# LCDTFT_CTRL_FT801.net
KiCad netlist of a schematic drawn in Altium Designer
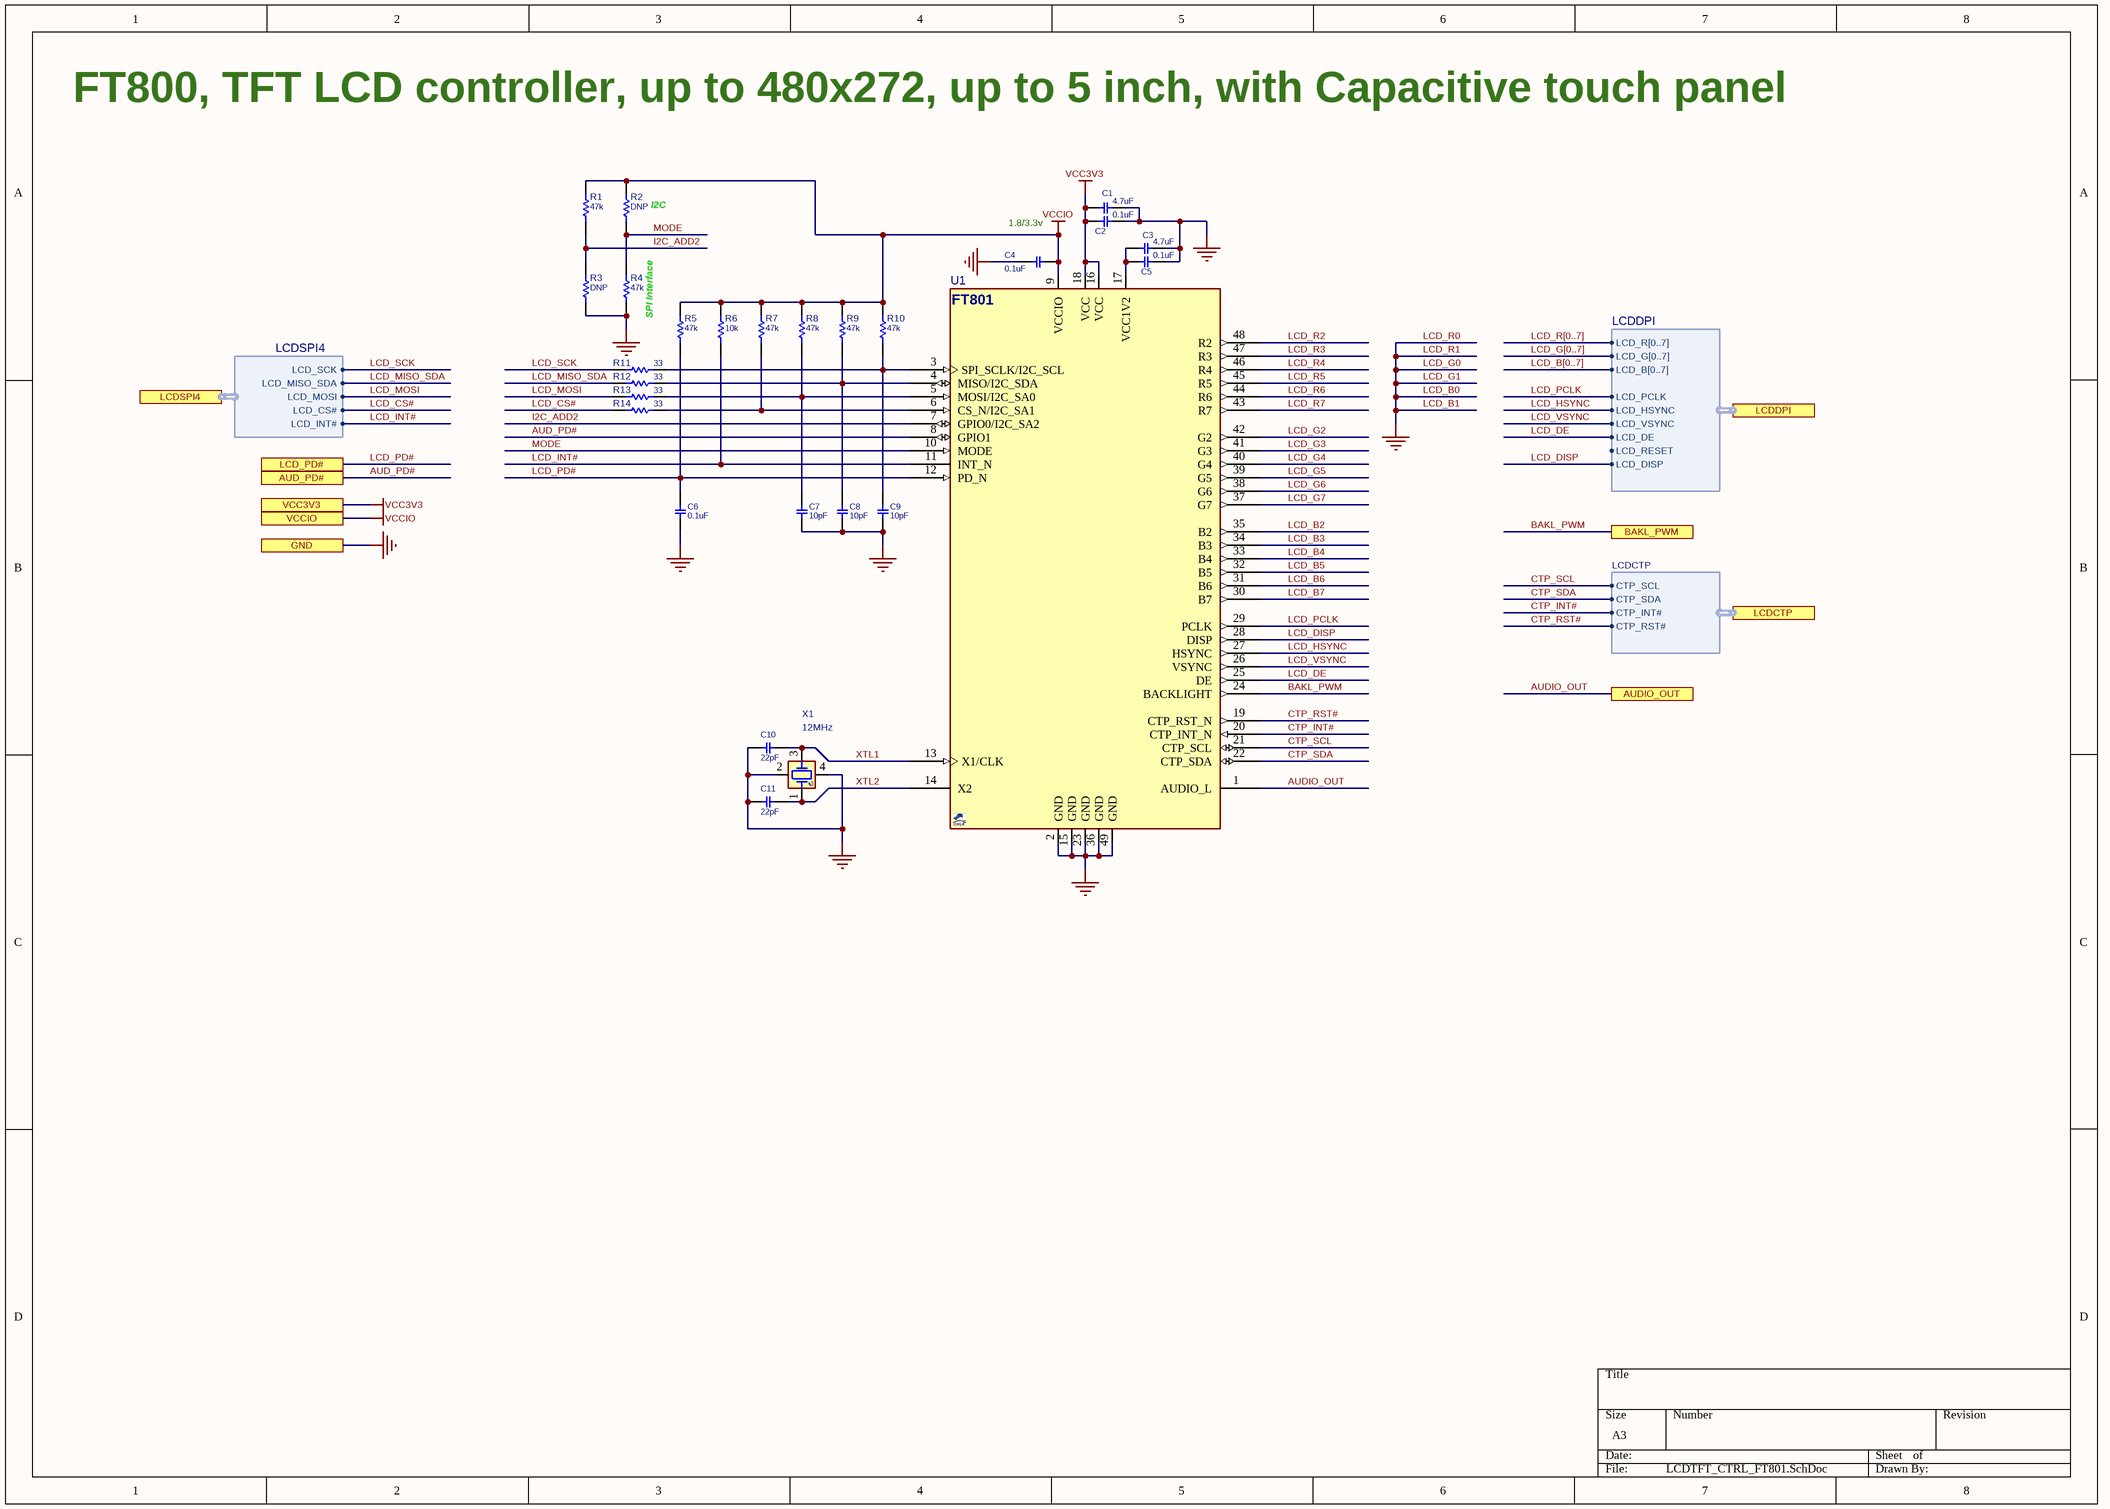
[diagram p0: LCDTFT_CTRL_FT801.SchDoc]

(export (version "E")
  (design (tool "Eeschema 10.0.6"))
  (components
    (comp (ref "C1")
      (value "4.7uF")
      (footprint "C0603")
      (description "CAP, MLCC")
      (libsource (lib "passive_smd") (part "CAP_SMD_MLCC"))
    )
    (comp (ref "C2")
      (value "0.1uF")
      (footprint "C0402")
      (description "CAP, MLCC")
      (fields (field (name "MANF_P#") "GRM155R71H104KE14D") (field (name "MANF") "Murata"))
      (libsource (lib "passive_smd") (part "CAP_SMD_MLCC"))
    )
    (comp (ref "C3")
      (value "4.7uF")
      (footprint "C0603")
      (description "CAP, MLCC")
      (libsource (lib "passive_smd") (part "CAP_SMD_MLCC"))
    )
    (comp (ref "C4")
      (value "0.1uF")
      (footprint "C0402")
      (description "CAP, MLCC")
      (fields (field (name "MANF_P#") "GRM155R71H104KE14D") (field (name "MANF") "Murata"))
      (libsource (lib "passive_smd") (part "CAP_SMD_MLCC"))
    )
    (comp (ref "C5")
      (value "0.1uF")
      (footprint "C0402")
      (description "CAP, MLCC")
      (fields (field (name "MANF_P#") "GRM155R71H104KE14D") (field (name "MANF") "Murata"))
      (libsource (lib "passive_smd") (part "CAP_SMD_MLCC"))
    )
    (comp (ref "C6")
      (value "0.1uF")
      (footprint "C0402")
      (description "CAP, MLCC")
      (fields (field (name "MANF_P#") "GRM155R71H104KE14D") (field (name "MANF") "Murata"))
      (libsource (lib "passive_smd") (part "CAP_SMD_MLCC"))
    )
    (comp (ref "C7")
      (value "10pF")
      (footprint "C0402")
      (description "CAP, MLCC")
      (libsource (lib "passive_smd") (part "CAP_SMD_MLCC"))
    )
    (comp (ref "C8")
      (value "10pF")
      (footprint "C0402")
      (description "CAP, MLCC")
      (libsource (lib "passive_smd") (part "CAP_SMD_MLCC"))
    )
    (comp (ref "C9")
      (value "10pF")
      (footprint "C0402")
      (description "CAP, MLCC")
      (libsource (lib "passive_smd") (part "CAP_SMD_MLCC"))
    )
    (comp (ref "C10")
      (value "22pF")
      (footprint "C0402")
      (description "CAP, MLCC")
      (libsource (lib "passive_smd") (part "CAP_SMD_MLCC"))
    )
    (comp (ref "C11")
      (value "22pF")
      (footprint "C0402")
      (description "CAP, MLCC")
      (libsource (lib "passive_smd") (part "CAP_SMD_MLCC"))
    )
    (comp (ref "R1")
      (value "47k")
      (footprint "R0402")
      (description "RESISTOR, SMD")
      (libsource (lib "passive_res_smd") (part "RES_SMD"))
    )
    (comp (ref "R2")
      (value "DNP")
      (footprint "R0402")
      (description "RESISTOR, SMD")
      (libsource (lib "passive_res_smd") (part "RES_SMD"))
    )
    (comp (ref "R3")
      (value "DNP")
      (footprint "R0402")
      (description "RESISTOR, SMD")
      (libsource (lib "passive_res_smd") (part "RES_SMD"))
    )
    (comp (ref "R4")
      (value "47k")
      (footprint "R0402")
      (description "RESISTOR, SMD")
      (libsource (lib "passive_res_smd") (part "RES_SMD"))
    )
    (comp (ref "R5")
      (value "47k")
      (footprint "R0402")
      (description "RESISTOR, SMD")
      (libsource (lib "passive_res_smd") (part "RES_SMD"))
    )
    (comp (ref "R6")
      (value "10k")
      (footprint "R0402")
      (description "RESISTOR, SMD")
      (libsource (lib "passive_res_smd") (part "RES_SMD"))
    )
    (comp (ref "R7")
      (value "47k")
      (footprint "R0402")
      (description "RESISTOR, SMD")
      (libsource (lib "passive_res_smd") (part "RES_SMD"))
    )
    (comp (ref "R8")
      (value "47k")
      (footprint "R0402")
      (description "RESISTOR, SMD")
      (libsource (lib "passive_res_smd") (part "RES_SMD"))
    )
    (comp (ref "R9")
      (value "47k")
      (footprint "R0402")
      (description "RESISTOR, SMD")
      (libsource (lib "passive_res_smd") (part "RES_SMD"))
    )
    (comp (ref "R10")
      (value "47k")
      (footprint "R0402")
      (description "RESISTOR, SMD")
      (libsource (lib "passive_res_smd") (part "RES_SMD"))
    )
    (comp (ref "R11")
      (value "33")
      (footprint "R0402")
      (description "RESISTOR, SMD")
      (libsource (lib "passive_res_smd") (part "RES_SMD"))
    )
    (comp (ref "R12")
      (value "33")
      (footprint "R0402")
      (description "RESISTOR, SMD")
      (libsource (lib "passive_res_smd") (part "RES_SMD"))
    )
    (comp (ref "R13")
      (value "33")
      (footprint "R0402")
      (description "RESISTOR, SMD")
      (libsource (lib "passive_res_smd") (part "RES_SMD"))
    )
    (comp (ref "R14")
      (value "33")
      (footprint "R0402")
      (description "RESISTOR, SMD")
      (libsource (lib "passive_res_smd") (part "RES_SMD"))
    )
    (comp (ref "U1")
      (value "FT801")
      (footprint "QFN50_48T")
      (description "LCD Display Controller, Embedded Video Engine, QFN-48")
      (fields (field (name "MANF") "FTDI/Bridgetek") (field (name "MANF_P#") "FT801Q"))
      (libsource (lib "lcdtft_controller") (part "FT801_QFN48"))
    )
    (comp (ref "X1")
      (value "12MHz")
      (footprint "XTL_4_3225")
      (description "Crystal 12MHz")
      (fields (field (name "MANF") "ECS") (field (name "MANF_P#") "ECS-120-18-33-JEM-TR"))
      (libsource (lib "crystal") (part "XTL_4_12MHz_3225"))
    )
  )
  (nets
    (net (code "4") (name "/AUDIO_OUT") (class "Default")
      (node (ref "U1") (pin "1") (pinfunction "AUDIO_L_1") (pintype "tri_state"))
    )
    (net (code "5") (name "/AUD_PD#") (class "Default")
      (node (ref "U1") (pin "8") (pinfunction "GPIO1_8") (pintype "bidirectional"))
    )
    (net (code "6") (name "/BAKL_PWM") (class "Default")
      (node (ref "U1") (pin "24") (pinfunction "BACKLIGHT_24") (pintype "output"))
    )
    (net (code "7") (name "/CTP_INT#") (class "Default")
      (node (ref "U1") (pin "20") (pinfunction "CTP_INT_N_20") (pintype "input"))
    )
    (net (code "8") (name "/CTP_RST#") (class "Default")
      (node (ref "U1") (pin "19") (pinfunction "CTP_RST_N_19") (pintype "output"))
    )
    (net (code "9") (name "/CTP_SCL") (class "Default")
      (node (ref "U1") (pin "21") (pinfunction "CTP_SCL_21") (pintype "bidirectional"))
    )
    (net (code "10") (name "/CTP_SDA") (class "Default")
      (node (ref "U1") (pin "22") (pinfunction "CTP_SDA_22") (pintype "bidirectional"))
    )
    (net (code "11") (name "/I2C_ADD2") (class "Default")
      (node (ref "R1") (pin "2") (pinfunction "2_2") (pintype "passive"))
      (node (ref "R3") (pin "1") (pinfunction "1_1") (pintype "passive"))
      (node (ref "U1") (pin "7") (pinfunction "GPIO0/I2C_SA2_7") (pintype "bidirectional"))
    )
    (net (code "12") (name "/LCD_B2") (class "Default")
      (node (ref "U1") (pin "35") (pinfunction "B2_35") (pintype "output"))
    )
    (net (code "13") (name "/LCD_B3") (class "Default")
      (node (ref "U1") (pin "34") (pinfunction "B3_34") (pintype "output"))
    )
    (net (code "14") (name "/LCD_B4") (class "Default")
      (node (ref "U1") (pin "33") (pinfunction "B4_33") (pintype "output"))
    )
    (net (code "15") (name "/LCD_B5") (class "Default")
      (node (ref "U1") (pin "32") (pinfunction "B5_32") (pintype "output"))
    )
    (net (code "16") (name "/LCD_B6") (class "Default")
      (node (ref "U1") (pin "31") (pinfunction "B6_31") (pintype "output"))
    )
    (net (code "17") (name "/LCD_B7") (class "Default")
      (node (ref "U1") (pin "30") (pinfunction "B7_30") (pintype "output"))
    )
    (net (code "19") (name "/LCD_CS#") (class "Default")
      (node (ref "R14") (pin "1") (pinfunction "1_1") (pintype "passive"))
    )
    (net (code "20") (name "/LCD_DE") (class "Default")
      (node (ref "U1") (pin "25") (pinfunction "DE_25") (pintype "output"))
    )
    (net (code "21") (name "/LCD_DISP") (class "Default")
      (node (ref "U1") (pin "28") (pinfunction "DISP_28") (pintype "output"))
    )
    (net (code "22") (name "/LCD_G2") (class "Default")
      (node (ref "U1") (pin "42") (pinfunction "G2_42") (pintype "output"))
    )
    (net (code "23") (name "/LCD_G3") (class "Default")
      (node (ref "U1") (pin "41") (pinfunction "G3_41") (pintype "output"))
    )
    (net (code "24") (name "/LCD_G4") (class "Default")
      (node (ref "U1") (pin "40") (pinfunction "G4_40") (pintype "output"))
    )
    (net (code "25") (name "/LCD_G5") (class "Default")
      (node (ref "U1") (pin "39") (pinfunction "G5_39") (pintype "output"))
    )
    (net (code "26") (name "/LCD_G6") (class "Default")
      (node (ref "U1") (pin "38") (pinfunction "G6_38") (pintype "output"))
    )
    (net (code "27") (name "/LCD_G7") (class "Default")
      (node (ref "U1") (pin "37") (pinfunction "G7_37") (pintype "output"))
    )
    (net (code "29") (name "/LCD_HSYNC") (class "Default")
      (node (ref "U1") (pin "27") (pinfunction "HSYNC_27") (pintype "output"))
    )
    (net (code "30") (name "/LCD_INT#") (class "Default")
      (node (ref "R6") (pin "2") (pinfunction "2_2") (pintype "passive"))
      (node (ref "U1") (pin "11") (pinfunction "INT_N_11") (pintype "tri_state"))
    )
    (net (code "31") (name "/LCD_MISO_SDA") (class "Default")
      (node (ref "R12") (pin "1") (pinfunction "1_1") (pintype "passive"))
    )
    (net (code "32") (name "/LCD_MOSI") (class "Default")
      (node (ref "R13") (pin "1") (pinfunction "1_1") (pintype "passive"))
    )
    (net (code "33") (name "/LCD_PCLK") (class "Default")
      (node (ref "U1") (pin "29") (pinfunction "PCLK_29") (pintype "output"))
    )
    (net (code "34") (name "/LCD_PD#") (class "Default")
      (node (ref "C6") (pin "1") (pinfunction "1_1") (pintype "passive"))
      (node (ref "R5") (pin "2") (pinfunction "2_2") (pintype "passive"))
      (node (ref "U1") (pin "12") (pinfunction "PD_N_12") (pintype "input"))
    )
    (net (code "35") (name "/LCD_R2") (class "Default")
      (node (ref "U1") (pin "48") (pinfunction "R2_48") (pintype "output"))
    )
    (net (code "36") (name "/LCD_R3") (class "Default")
      (node (ref "U1") (pin "47") (pinfunction "R3_47") (pintype "output"))
    )
    (net (code "37") (name "/LCD_R4") (class "Default")
      (node (ref "U1") (pin "46") (pinfunction "R4_46") (pintype "output"))
    )
    (net (code "38") (name "/LCD_R5") (class "Default")
      (node (ref "U1") (pin "45") (pinfunction "R5_45") (pintype "output"))
    )
    (net (code "39") (name "/LCD_R6") (class "Default")
      (node (ref "U1") (pin "44") (pinfunction "R6_44") (pintype "output"))
    )
    (net (code "40") (name "/LCD_R7") (class "Default")
      (node (ref "U1") (pin "43") (pinfunction "R7_43") (pintype "output"))
    )
    (net (code "42") (name "/LCD_SCK") (class "Default")
      (node (ref "R11") (pin "1") (pinfunction "1_1") (pintype "passive"))
    )
    (net (code "43") (name "/LCD_VSYNC") (class "Default")
      (node (ref "U1") (pin "26") (pinfunction "VSYNC_26") (pintype "output"))
    )
    (net (code "44") (name "/MODE") (class "Default")
      (node (ref "R2") (pin "2") (pinfunction "2_2") (pintype "passive"))
      (node (ref "R4") (pin "1") (pinfunction "1_1") (pintype "passive"))
      (node (ref "U1") (pin "10") (pinfunction "MODE_10") (pintype "input"))
    )
    (net (code "45") (name "/XTL1") (class "Default")
      (node (ref "C10") (pin "2") (pinfunction "2_2") (pintype "passive"))
      (node (ref "U1") (pin "13") (pinfunction "X1/CLK_13") (pintype "input"))
      (node (ref "X1") (pin "3") (pinfunction "2_3") (pintype "passive"))
    )
    (net (code "46") (name "/XTL2") (class "Default")
      (node (ref "C11") (pin "1") (pinfunction "1_1") (pintype "passive"))
      (node (ref "U1") (pin "14") (pinfunction "X2_14") (pintype "passive"))
      (node (ref "X1") (pin "1") (pinfunction "1_1") (pintype "passive"))
    )
    (net (code "50") (name "GND") (class "Default")
      (node (ref "C1") (pin "1") (pinfunction "1_1") (pintype "passive"))
      (node (ref "C10") (pin "1") (pinfunction "1_1") (pintype "passive"))
      (node (ref "C11") (pin "2") (pinfunction "2_2") (pintype "passive"))
      (node (ref "C2") (pin "1") (pinfunction "1_1") (pintype "passive"))
      (node (ref "C3") (pin "1") (pinfunction "1_1") (pintype "passive"))
      (node (ref "C4") (pin "2") (pinfunction "2_2") (pintype "passive"))
      (node (ref "C5") (pin "1") (pinfunction "1_1") (pintype "passive"))
      (node (ref "C6") (pin "2") (pinfunction "2_2") (pintype "passive"))
      (node (ref "C7") (pin "2") (pinfunction "2_2") (pintype "passive"))
      (node (ref "C8") (pin "2") (pinfunction "2_2") (pintype "passive"))
      (node (ref "C9") (pin "2") (pinfunction "2_2") (pintype "passive"))
      (node (ref "R3") (pin "2") (pinfunction "2_2") (pintype "passive"))
      (node (ref "R4") (pin "2") (pinfunction "2_2") (pintype "passive"))
      (node (ref "U1") (pin "15") (pinfunction "GND_15") (pintype "power_in"))
      (node (ref "U1") (pin "2") (pinfunction "GND_2") (pintype "power_in"))
      (node (ref "U1") (pin "23") (pinfunction "GND_23") (pintype "power_in"))
      (node (ref "U1") (pin "36") (pinfunction "GND_36") (pintype "power_in"))
      (node (ref "U1") (pin "49") (pinfunction "GND_49") (pintype "power_in"))
      (node (ref "X1") (pin "2") (pinfunction "2_2") (pintype "passive"))
      (node (ref "X1") (pin "4") (pinfunction "4_4") (pintype "passive"))
    )
    (net (code "51") (name "Net-(U1-CS_N{slash}I2C_SA1)") (class "Default")
      (node (ref "R14") (pin "2") (pinfunction "2_2") (pintype "passive"))
      (node (ref "R7") (pin "2") (pinfunction "2_2") (pintype "passive"))
      (node (ref "U1") (pin "6") (pinfunction "CS_N/I2C_SA1_6") (pintype "input"))
    )
    (net (code "52") (name "Net-(U1-MISO{slash}I2C_SDA)") (class "Default")
      (node (ref "C8") (pin "1") (pinfunction "1_1") (pintype "passive"))
      (node (ref "R12") (pin "2") (pinfunction "2_2") (pintype "passive"))
      (node (ref "R9") (pin "2") (pinfunction "2_2") (pintype "passive"))
      (node (ref "U1") (pin "4") (pinfunction "MISO/I2C_SDA_4") (pintype "bidirectional"))
    )
    (net (code "53") (name "Net-(U1-MOSI{slash}I2C_SA0)") (class "Default")
      (node (ref "C7") (pin "1") (pinfunction "1_1") (pintype "passive"))
      (node (ref "R13") (pin "2") (pinfunction "2_2") (pintype "passive"))
      (node (ref "R8") (pin "2") (pinfunction "2_2") (pintype "passive"))
      (node (ref "U1") (pin "5") (pinfunction "MOSI/I2C_SA0_5") (pintype "input"))
    )
    (net (code "54") (name "Net-(U1-SPI_SCLK{slash}I2C_SCL)") (class "Default")
      (node (ref "C9") (pin "1") (pinfunction "1_1") (pintype "passive"))
      (node (ref "R10") (pin "2") (pinfunction "2_2") (pintype "passive"))
      (node (ref "R11") (pin "2") (pinfunction "2_2") (pintype "passive"))
      (node (ref "U1") (pin "3") (pinfunction "SPI_SCLK/I2C_SCL_3") (pintype "input"))
    )
    (net (code "55") (name "Net-(U1-VCC1V2)") (class "Default")
      (node (ref "C3") (pin "2") (pinfunction "2_2") (pintype "passive"))
      (node (ref "C5") (pin "2") (pinfunction "2_2") (pintype "passive"))
      (node (ref "U1") (pin "17") (pinfunction "VCC1V2_17") (pintype "power_in"))
    )
    (net (code "56") (name "VCC3V3") (class "Default")
      (node (ref "C1") (pin "2") (pinfunction "2_2") (pintype "passive"))
      (node (ref "C2") (pin "2") (pinfunction "2_2") (pintype "passive"))
      (node (ref "U1") (pin "16") (pinfunction "VCC_16") (pintype "power_in"))
      (node (ref "U1") (pin "18") (pinfunction "VCC_18") (pintype "power_in"))
    )
    (net (code "57") (name "VCCIO") (class "Default")
      (node (ref "C4") (pin "1") (pinfunction "1_1") (pintype "passive"))
      (node (ref "R1") (pin "1") (pinfunction "1_1") (pintype "passive"))
      (node (ref "R10") (pin "1") (pinfunction "1_1") (pintype "passive"))
      (node (ref "R2") (pin "1") (pinfunction "1_1") (pintype "passive"))
      (node (ref "R5") (pin "1") (pinfunction "1_1") (pintype "passive"))
      (node (ref "R6") (pin "1") (pinfunction "1_1") (pintype "passive"))
      (node (ref "R7") (pin "1") (pinfunction "1_1") (pintype "passive"))
      (node (ref "R8") (pin "1") (pinfunction "1_1") (pintype "passive"))
      (node (ref "R9") (pin "1") (pinfunction "1_1") (pintype "passive"))
      (node (ref "U1") (pin "9") (pinfunction "VCCIO_9") (pintype "power_in"))
    )
  )
)
